# GPS_SATA.net
KiCad netlist of a schematic drawn in Altium Designer
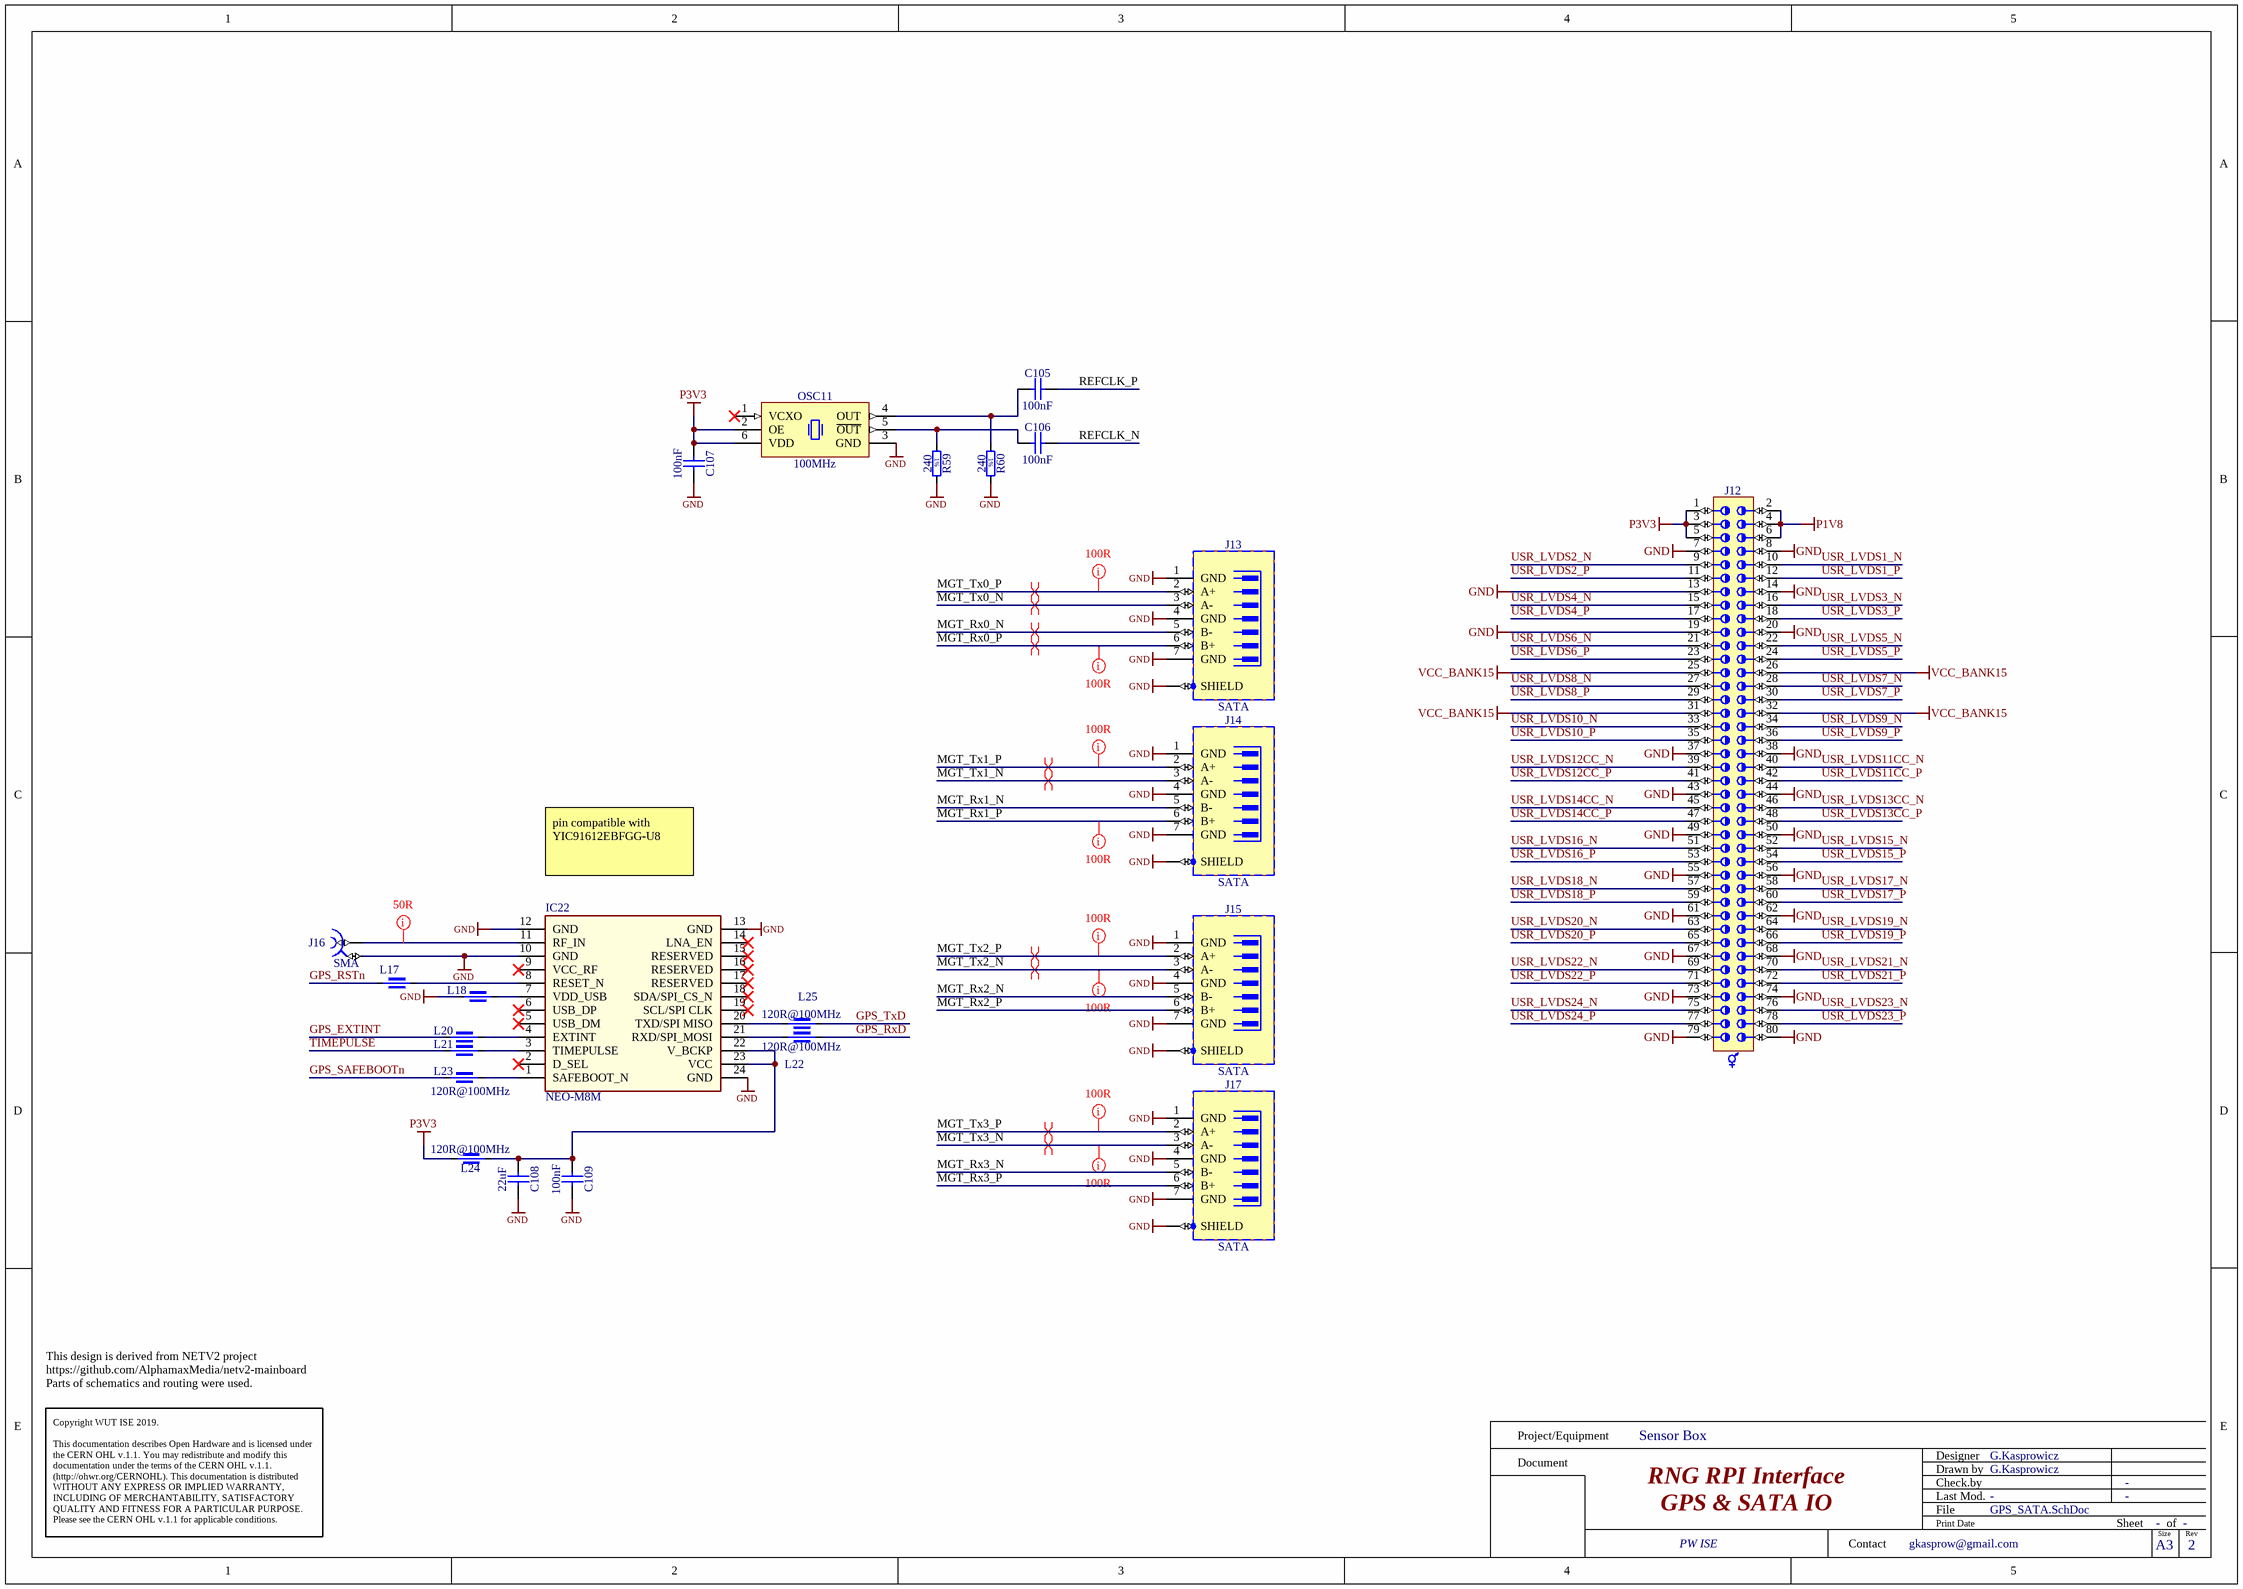
[diagram p0: GPS_SATA.SchDoc]

(export (version "E")
  (design (tool "Eeschema 10.0.6"))
  (components
    (comp (ref "C105")
      (value "100nF")
      (footprint "CAPC0603X33N")
      (description "Non-polarised capacitor")
      (fields
        (field (name "PART NUMBER") "CC0201_100NF_6.3V_10%_X5R")
        (field (name "VOLTAGE") "6.3V")
        (field (name "AUTHOR") "CERN DEM JLC")
      )
      (libsource (lib "Capacitors") (part "Capacitor - non polarized"))
    )
    (comp (ref "C106")
      (value "100nF")
      (footprint "CAPC0603X33N")
      (description "Non-polarised capacitor")
      (fields
        (field (name "PART NUMBER") "CC0201_100NF_6.3V_10%_X5R")
        (field (name "VOLTAGE") "6.3V")
        (field (name "AUTHOR") "CERN DEM JLC")
      )
      (libsource (lib "Capacitors") (part "Capacitor - non polarized"))
    )
    (comp (ref "C107")
      (value "100nF")
      (footprint "CAPC0603X33N")
      (description "Non-polarised capacitor")
      (fields
        (field (name "PART NUMBER") "CC0201_100NF_6.3V_10%_X5R")
        (field (name "VOLTAGE") "6.3V")
        (field (name "AUTHOR") "CERN DEM JLC")
      )
      (libsource (lib "Capacitors") (part "Capacitor - non polarized"))
    )
    (comp (ref "C108")
      (value "22uF")
      (footprint "CAPC2012X135N")
      (description "Non-polarised capacitor")
      (fields
        (field (name "PART NUMBER") "CC0805_22UF_16V_10%_X5R")
        (field (name "VOLTAGE") "16V")
        (field (name "AUTHOR") "CERN DEM JLC")
      )
      (libsource (lib "Capacitors") (part "Capacitor - non polarized"))
    )
    (comp (ref "C109")
      (value "100nF")
      (footprint "CAPC0603X33N")
      (description "Non-polarised capacitor")
      (fields
        (field (name "PART NUMBER") "CC0201_100NF_6.3V_10%_X5R")
        (field (name "VOLTAGE") "6.3V")
        (field (name "AUTHOR") "CERN DEM JLC")
      )
      (libsource (lib "Capacitors") (part "Capacitor - non polarized"))
    )
    (comp (ref "IC22")
      (value "NEO-M8M")
      (footprint "NEO")
      (description "u-blox NEO GNSS module")
      (fields (field (name "MANUFACTURER") "u-blox"))
      (libsource (lib "ubloxLib") (part "NEO"))
    )
    (comp (ref "J12")
      (value "~")
      (footprint "SAMTEC_LSS-140-01-L-DV-A")
      (description "Connector 80 Hermaphroditic")
      (fields
        (field (name "PART NUMBER") "SAMTEC_LSS-140-01-L-DV-A")
        (field (name "MANUFACTURER") "SAMTEC")
        (field (name "AUTHOR") "CERN DEM JMW")
      )
      (libsource (lib "Connectors") (part "Connector 80 Hermaphroditic"))
    )
    (comp (ref "J13")
      (value "SATA")
      (footprint "3M_5607-4200-SH")
      (description "7 Pin + 1 Shield SATA Receptacle")
      (fields
        (field (name "PART NUMBER") "3M_5607-4200-SH")
        (field (name "MANUFACTURER") "3M")
        (field (name "AUTHOR") "CERN DEM JLC")
      )
      (libsource (lib "Connectors") (part "Connector SATA 7 Male + 1 Shield"))
    )
    (comp (ref "J14")
      (value "SATA")
      (footprint "3M_5607-4200-SH")
      (description "7 Pin + 1 Shield SATA Receptacle")
      (fields
        (field (name "PART NUMBER") "3M_5607-4200-SH")
        (field (name "MANUFACTURER") "3M")
        (field (name "AUTHOR") "CERN DEM JLC")
      )
      (libsource (lib "Connectors") (part "Connector SATA 7 Male + 1 Shield"))
    )
    (comp (ref "J15")
      (value "SATA")
      (footprint "3M_5607-4200-SH")
      (description "7 Pin + 1 Shield SATA Receptacle")
      (fields
        (field (name "PART NUMBER") "3M_5607-4200-SH")
        (field (name "MANUFACTURER") "3M")
        (field (name "AUTHOR") "CERN DEM JLC")
      )
      (libsource (lib "Connectors") (part "Connector SATA 7 Male + 1 Shield"))
    )
    (comp (ref "J16")
      (value "SMA")
      (footprint "MOLEX_73251-2120")
      (description "50 Ohm, SMA Edge Mount PCB, With Jam Nut And Lock Washer")
      (fields
        (field (name "PART NUMBER") "MOLEX_73251-2120")
        (field (name "MANUFACTURER") "MOLEX")
        (field (name "AUTHOR") "CERN DEM JLC")
      )
      (libsource (lib "Connectors") (part "CON_SMA_RA_SMD_73251-2120"))
    )
    (comp (ref "J17")
      (value "SATA")
      (footprint "3M_5607-4200-SH")
      (description "7 Pin + 1 Shield SATA Receptacle")
      (fields
        (field (name "PART NUMBER") "3M_5607-4200-SH")
        (field (name "MANUFACTURER") "3M")
        (field (name "AUTHOR") "CERN DEM JLC")
      )
      (libsource (lib "Connectors") (part "Connector SATA 7 Male + 1 Shield"))
    )
    (comp (ref "L17")
      (value "120R@100MHz")
      (footprint "INDC1608X65N")
      (fields
        (field (name "PART NUMBER") "IND0603_MURATA_BLM18SG121TN1D")
        (field (name "POWER") "3A")
        (field (name "TOLERANCE") "±25%")
        (field (name "AUTHOR") "CERN DEM JLC")
      )
      (libsource (lib "") (part "Ferrite Bead_1"))
    )
    (comp (ref "L18")
      (value "120R@100MHz")
      (footprint "INDC1608X65N")
      (fields
        (field (name "PART NUMBER") "IND0603_MURATA_BLM18SG121TN1D")
        (field (name "POWER") "3A")
        (field (name "TOLERANCE") "±25%")
        (field (name "AUTHOR") "CERN DEM JLC")
      )
      (libsource (lib "Inductors & Transformers") (part "Ferrite Bead"))
    )
    (comp (ref "L20")
      (value "120R@100MHz")
      (footprint "INDC1608X65N")
      (fields
        (field (name "PART NUMBER") "IND0603_MURATA_BLM18SG121TN1D")
        (field (name "POWER") "3A")
        (field (name "TOLERANCE") "±25%")
        (field (name "AUTHOR") "CERN DEM JLC")
      )
      (libsource (lib "Inductors & Transformers") (part "Ferrite Bead"))
    )
    (comp (ref "L21")
      (value "120R@100MHz")
      (footprint "INDC1608X65N")
      (fields
        (field (name "PART NUMBER") "IND0603_MURATA_BLM18SG121TN1D")
        (field (name "POWER") "3A")
        (field (name "TOLERANCE") "±25%")
        (field (name "AUTHOR") "CERN DEM JLC")
      )
      (libsource (lib "Inductors & Transformers") (part "Ferrite Bead"))
    )
    (comp (ref "L22")
      (value "120R@100MHz")
      (footprint "INDC1608X65N")
      (fields
        (field (name "PART NUMBER") "IND0603_MURATA_BLM18SG121TN1D")
        (field (name "POWER") "3A")
        (field (name "TOLERANCE") "±25%")
        (field (name "AUTHOR") "CERN DEM JLC")
      )
      (libsource (lib "") (part "Ferrite Bead_1"))
    )
    (comp (ref "L23")
      (value "120R@100MHz")
      (footprint "INDC1608X65N")
      (fields
        (field (name "PART NUMBER") "IND0603_MURATA_BLM18SG121TN1D")
        (field (name "POWER") "3A")
        (field (name "TOLERANCE") "±25%")
        (field (name "AUTHOR") "CERN DEM JLC")
      )
      (libsource (lib "Inductors & Transformers") (part "Ferrite Bead"))
    )
    (comp (ref "L24")
      (value "120R@100MHz")
      (footprint "INDC1608X65N")
      (fields
        (field (name "PART NUMBER") "IND0603_MURATA_BLM18SG121TN1D")
        (field (name "POWER") "3A")
        (field (name "TOLERANCE") "±25%")
        (field (name "AUTHOR") "CERN DEM JLC")
      )
      (libsource (lib "Inductors & Transformers") (part "Ferrite Bead"))
    )
    (comp (ref "L25")
      (value "120R@100MHz")
      (footprint "INDC1608X65N")
      (fields
        (field (name "PART NUMBER") "IND0603_MURATA_BLM18SG121TN1D")
        (field (name "POWER") "3A")
        (field (name "TOLERANCE") "±25%")
        (field (name "AUTHOR") "CERN DEM JLC")
      )
      (libsource (lib "Inductors & Transformers") (part "Ferrite Bead"))
    )
    (comp (ref "OSC11")
      (value "100MHz")
      (footprint "OSCSC254P500X700X190-6N")
      (description "VCXO 100MHz Oscillator")
      (fields
        (field (name "PART NUMBER") "OSC_100MHZ_ABRACON_ASG-P-V-A-100.000MHZ")
        (field (name "MANUFACTURER") "ABRACON")
        (field (name "AUTHOR") "GK")
      )
      (libsource (lib "Crystals_Oscillators") (part "OSC_100MHz_LVPECL"))
    )
    (comp (ref "R59")
      (value "240")
      (footprint "RESC1005X40N")
      (description "Resistor - 1%")
      (fields
        (field (name "PART NUMBER") "R0402_240R_1%_0.0625W_100PPM")
        (field (name "POWER") "0.0625W")
        (field (name "AUTHOR") "CERN DEM JLC")
      )
      (libsource (lib "Resistors") (part "Resistor - 1%"))
    )
    (comp (ref "R60")
      (value "240")
      (footprint "RESC1005X40N")
      (description "Resistor - 1%")
      (fields
        (field (name "PART NUMBER") "R0402_240R_1%_0.0625W_100PPM")
        (field (name "POWER") "0.0625W")
        (field (name "AUTHOR") "CERN DEM JLC")
      )
      (libsource (lib "Resistors") (part "Resistor - 1%"))
    )
  )
  (nets
    (net (code "1") (name "/GPS_EXTINT") (class "Default")
      (node (ref "L20") (pin "2") (pinfunction "2_2") (pintype "passive"))
    )
    (net (code "2") (name "/GPS_RSTn") (class "Default")
      (node (ref "L17") (pin "1") (pinfunction "1_1") (pintype "passive"))
    )
    (net (code "3") (name "/GPS_RxD") (class "Default")
      (node (ref "L22") (pin "2") (pinfunction "2_2") (pintype "passive"))
    )
    (net (code "4") (name "/GPS_SAFEBOOTn") (class "Default")
      (node (ref "L23") (pin "2") (pinfunction "2_2") (pintype "passive"))
    )
    (net (code "5") (name "/GPS_TxD") (class "Default")
      (node (ref "L25") (pin "1") (pinfunction "1_1") (pintype "passive"))
    )
    (net (code "6") (name "/MGT_Rx0_N") (class "Default")
      (node (ref "J13") (pin "5") (pinfunction "B-_5") (pintype "bidirectional"))
    )
    (net (code "7") (name "/MGT_Rx0_P") (class "Default")
      (node (ref "J13") (pin "6") (pinfunction "B+_6") (pintype "bidirectional"))
    )
    (net (code "8") (name "/MGT_Rx1_N") (class "Default")
      (node (ref "J14") (pin "5") (pinfunction "B-_5") (pintype "bidirectional"))
    )
    (net (code "9") (name "/MGT_Rx1_P") (class "Default")
      (node (ref "J14") (pin "6") (pinfunction "B+_6") (pintype "bidirectional"))
    )
    (net (code "10") (name "/MGT_Rx2_N") (class "Default")
      (node (ref "J15") (pin "5") (pinfunction "B-_5") (pintype "bidirectional"))
    )
    (net (code "11") (name "/MGT_Rx2_P") (class "Default")
      (node (ref "J15") (pin "6") (pinfunction "B+_6") (pintype "bidirectional"))
    )
    (net (code "12") (name "/MGT_Rx3_N") (class "Default")
      (node (ref "J17") (pin "5") (pinfunction "B-_5") (pintype "bidirectional"))
    )
    (net (code "13") (name "/MGT_Rx3_P") (class "Default")
      (node (ref "J17") (pin "6") (pinfunction "B+_6") (pintype "bidirectional"))
    )
    (net (code "14") (name "/MGT_Tx0_N") (class "Default")
      (node (ref "J13") (pin "3") (pinfunction "A-_3") (pintype "bidirectional"))
    )
    (net (code "15") (name "/MGT_Tx0_P") (class "Default")
      (node (ref "J13") (pin "2") (pinfunction "A+_2") (pintype "bidirectional"))
    )
    (net (code "16") (name "/MGT_Tx1_N") (class "Default")
      (node (ref "J14") (pin "3") (pinfunction "A-_3") (pintype "bidirectional"))
    )
    (net (code "17") (name "/MGT_Tx1_P") (class "Default")
      (node (ref "J14") (pin "2") (pinfunction "A+_2") (pintype "bidirectional"))
    )
    (net (code "18") (name "/MGT_Tx2_N") (class "Default")
      (node (ref "J15") (pin "3") (pinfunction "A-_3") (pintype "bidirectional"))
    )
    (net (code "19") (name "/MGT_Tx2_P") (class "Default")
      (node (ref "J15") (pin "2") (pinfunction "A+_2") (pintype "bidirectional"))
    )
    (net (code "20") (name "/MGT_Tx3_N") (class "Default")
      (node (ref "J17") (pin "3") (pinfunction "A-_3") (pintype "bidirectional"))
    )
    (net (code "21") (name "/MGT_Tx3_P") (class "Default")
      (node (ref "J17") (pin "2") (pinfunction "A+_2") (pintype "bidirectional"))
    )
    (net (code "22") (name "/REFCLK_N") (class "Default")
      (node (ref "C106") (pin "2") (pinfunction "2_2") (pintype "passive"))
    )
    (net (code "23") (name "/REFCLK_P") (class "Default")
      (node (ref "C105") (pin "2") (pinfunction "2_2") (pintype "passive"))
    )
    (net (code "24") (name "/TIMEPULSE") (class "Default")
      (node (ref "L21") (pin "2") (pinfunction "2_2") (pintype "passive"))
    )
    (net (code "25") (name "/USR_LVDS1_N") (class "Default")
      (node (ref "J12") (pin "10") (pinfunction "10_10") (pintype "bidirectional"))
    )
    (net (code "26") (name "/USR_LVDS1_P") (class "Default")
      (node (ref "J12") (pin "12") (pinfunction "12_12") (pintype "bidirectional"))
    )
    (net (code "27") (name "/USR_LVDS2_N") (class "Default")
      (node (ref "J12") (pin "9") (pinfunction "9_9") (pintype "bidirectional"))
    )
    (net (code "28") (name "/USR_LVDS2_P") (class "Default")
      (node (ref "J12") (pin "11") (pinfunction "11_11") (pintype "bidirectional"))
    )
    (net (code "29") (name "/USR_LVDS3_N") (class "Default")
      (node (ref "J12") (pin "16") (pinfunction "16_16") (pintype "bidirectional"))
    )
    (net (code "30") (name "/USR_LVDS3_P") (class "Default")
      (node (ref "J12") (pin "18") (pinfunction "18_18") (pintype "bidirectional"))
    )
    (net (code "31") (name "/USR_LVDS4_N") (class "Default")
      (node (ref "J12") (pin "15") (pinfunction "15_15") (pintype "bidirectional"))
    )
    (net (code "32") (name "/USR_LVDS4_P") (class "Default")
      (node (ref "J12") (pin "17") (pinfunction "17_17") (pintype "bidirectional"))
    )
    (net (code "33") (name "/USR_LVDS5_N") (class "Default")
      (node (ref "J12") (pin "22") (pinfunction "22_22") (pintype "bidirectional"))
    )
    (net (code "34") (name "/USR_LVDS5_P") (class "Default")
      (node (ref "J12") (pin "24") (pinfunction "24_24") (pintype "bidirectional"))
    )
    (net (code "35") (name "/USR_LVDS6_N") (class "Default")
      (node (ref "J12") (pin "21") (pinfunction "21_21") (pintype "bidirectional"))
    )
    (net (code "36") (name "/USR_LVDS6_P") (class "Default")
      (node (ref "J12") (pin "23") (pinfunction "23_23") (pintype "bidirectional"))
    )
    (net (code "37") (name "/USR_LVDS7_N") (class "Default")
      (node (ref "J12") (pin "28") (pinfunction "28_28") (pintype "bidirectional"))
    )
    (net (code "38") (name "/USR_LVDS7_P") (class "Default")
      (node (ref "J12") (pin "30") (pinfunction "30_30") (pintype "bidirectional"))
    )
    (net (code "39") (name "/USR_LVDS8_N") (class "Default")
      (node (ref "J12") (pin "27") (pinfunction "27_27") (pintype "bidirectional"))
    )
    (net (code "40") (name "/USR_LVDS8_P") (class "Default")
      (node (ref "J12") (pin "29") (pinfunction "29_29") (pintype "bidirectional"))
    )
    (net (code "41") (name "/USR_LVDS9_N") (class "Default")
      (node (ref "J12") (pin "34") (pinfunction "34_34") (pintype "bidirectional"))
    )
    (net (code "42") (name "/USR_LVDS9_P") (class "Default")
      (node (ref "J12") (pin "36") (pinfunction "36_36") (pintype "bidirectional"))
    )
    (net (code "43") (name "/USR_LVDS10_N") (class "Default")
      (node (ref "J12") (pin "33") (pinfunction "33_33") (pintype "bidirectional"))
    )
    (net (code "44") (name "/USR_LVDS10_P") (class "Default")
      (node (ref "J12") (pin "35") (pinfunction "35_35") (pintype "bidirectional"))
    )
    (net (code "45") (name "/USR_LVDS11CC_N") (class "Default")
      (node (ref "J12") (pin "40") (pinfunction "40_40") (pintype "bidirectional"))
    )
    (net (code "46") (name "/USR_LVDS11CC_P") (class "Default")
      (node (ref "J12") (pin "42") (pinfunction "42_42") (pintype "bidirectional"))
    )
    (net (code "47") (name "/USR_LVDS12CC_N") (class "Default")
      (node (ref "J12") (pin "39") (pinfunction "39_39") (pintype "bidirectional"))
    )
    (net (code "48") (name "/USR_LVDS12CC_P") (class "Default")
      (node (ref "J12") (pin "41") (pinfunction "41_41") (pintype "bidirectional"))
    )
    (net (code "49") (name "/USR_LVDS13CC_N") (class "Default")
      (node (ref "J12") (pin "46") (pinfunction "46_46") (pintype "bidirectional"))
    )
    (net (code "50") (name "/USR_LVDS13CC_P") (class "Default")
      (node (ref "J12") (pin "48") (pinfunction "48_48") (pintype "bidirectional"))
    )
    (net (code "51") (name "/USR_LVDS14CC_N") (class "Default")
      (node (ref "J12") (pin "45") (pinfunction "45_45") (pintype "bidirectional"))
    )
    (net (code "52") (name "/USR_LVDS14CC_P") (class "Default")
      (node (ref "J12") (pin "47") (pinfunction "47_47") (pintype "bidirectional"))
    )
    (net (code "53") (name "/USR_LVDS15_N") (class "Default")
      (node (ref "J12") (pin "52") (pinfunction "52_52") (pintype "bidirectional"))
    )
    (net (code "54") (name "/USR_LVDS15_P") (class "Default")
      (node (ref "J12") (pin "54") (pinfunction "54_54") (pintype "bidirectional"))
    )
    (net (code "55") (name "/USR_LVDS16_N") (class "Default")
      (node (ref "J12") (pin "51") (pinfunction "51_51") (pintype "bidirectional"))
    )
    (net (code "56") (name "/USR_LVDS16_P") (class "Default")
      (node (ref "J12") (pin "53") (pinfunction "53_53") (pintype "bidirectional"))
    )
    (net (code "57") (name "/USR_LVDS17_N") (class "Default")
      (node (ref "J12") (pin "58") (pinfunction "58_58") (pintype "bidirectional"))
    )
    (net (code "58") (name "/USR_LVDS17_P") (class "Default")
      (node (ref "J12") (pin "60") (pinfunction "60_60") (pintype "bidirectional"))
    )
    (net (code "59") (name "/USR_LVDS18_N") (class "Default")
      (node (ref "J12") (pin "57") (pinfunction "57_57") (pintype "bidirectional"))
    )
    (net (code "60") (name "/USR_LVDS18_P") (class "Default")
      (node (ref "J12") (pin "59") (pinfunction "59_59") (pintype "bidirectional"))
    )
    (net (code "61") (name "/USR_LVDS19_N") (class "Default")
      (node (ref "J12") (pin "64") (pinfunction "64_64") (pintype "bidirectional"))
    )
    (net (code "62") (name "/USR_LVDS19_P") (class "Default")
      (node (ref "J12") (pin "66") (pinfunction "66_66") (pintype "bidirectional"))
    )
    (net (code "63") (name "/USR_LVDS20_N") (class "Default")
      (node (ref "J12") (pin "63") (pinfunction "63_63") (pintype "bidirectional"))
    )
    (net (code "64") (name "/USR_LVDS20_P") (class "Default")
      (node (ref "J12") (pin "65") (pinfunction "65_65") (pintype "bidirectional"))
    )
    (net (code "65") (name "/USR_LVDS21_N") (class "Default")
      (node (ref "J12") (pin "70") (pinfunction "70_70") (pintype "bidirectional"))
    )
    (net (code "66") (name "/USR_LVDS21_P") (class "Default")
      (node (ref "J12") (pin "72") (pinfunction "72_72") (pintype "bidirectional"))
    )
    (net (code "67") (name "/USR_LVDS22_N") (class "Default")
      (node (ref "J12") (pin "69") (pinfunction "69_69") (pintype "bidirectional"))
    )
    (net (code "68") (name "/USR_LVDS22_P") (class "Default")
      (node (ref "J12") (pin "71") (pinfunction "71_71") (pintype "bidirectional"))
    )
    (net (code "69") (name "/USR_LVDS23_N") (class "Default")
      (node (ref "J12") (pin "76") (pinfunction "76_76") (pintype "bidirectional"))
    )
    (net (code "70") (name "/USR_LVDS23_P") (class "Default")
      (node (ref "J12") (pin "78") (pinfunction "78_78") (pintype "bidirectional"))
    )
    (net (code "71") (name "/USR_LVDS24_N") (class "Default")
      (node (ref "J12") (pin "75") (pinfunction "75_75") (pintype "bidirectional"))
    )
    (net (code "72") (name "/USR_LVDS24_P") (class "Default")
      (node (ref "J12") (pin "77") (pinfunction "77_77") (pintype "bidirectional"))
    )
    (net (code "73") (name "GND") (class "Default")
      (node (ref "C107") (pin "2") (pinfunction "2_2") (pintype "passive"))
      (node (ref "C108") (pin "2") (pinfunction "2_2") (pintype "passive"))
      (node (ref "C109") (pin "2") (pinfunction "2_2") (pintype "passive"))
      (node (ref "IC22") (pin "10") (pinfunction "GND_10") (pintype "passive"))
      (node (ref "IC22") (pin "12") (pinfunction "GND_12") (pintype "passive"))
      (node (ref "IC22") (pin "13") (pinfunction "GND_13") (pintype "passive"))
      (node (ref "IC22") (pin "24") (pinfunction "GND_24") (pintype "passive"))
      (node (ref "J12") (pin "13") (pinfunction "13_13") (pintype "bidirectional"))
      (node (ref "J12") (pin "14") (pinfunction "14_14") (pintype "bidirectional"))
      (node (ref "J12") (pin "19") (pinfunction "19_19") (pintype "bidirectional"))
      (node (ref "J12") (pin "20") (pinfunction "20_20") (pintype "bidirectional"))
      (node (ref "J12") (pin "37") (pinfunction "37_37") (pintype "bidirectional"))
      (node (ref "J12") (pin "38") (pinfunction "38_38") (pintype "bidirectional"))
      (node (ref "J12") (pin "43") (pinfunction "43_43") (pintype "bidirectional"))
      (node (ref "J12") (pin "44") (pinfunction "44_44") (pintype "bidirectional"))
      (node (ref "J12") (pin "49") (pinfunction "49_49") (pintype "bidirectional"))
      (node (ref "J12") (pin "50") (pinfunction "50_50") (pintype "bidirectional"))
      (node (ref "J12") (pin "55") (pinfunction "55_55") (pintype "bidirectional"))
      (node (ref "J12") (pin "56") (pinfunction "56_56") (pintype "bidirectional"))
      (node (ref "J12") (pin "61") (pinfunction "61_61") (pintype "bidirectional"))
      (node (ref "J12") (pin "62") (pinfunction "62_62") (pintype "bidirectional"))
      (node (ref "J12") (pin "67") (pinfunction "67_67") (pintype "bidirectional"))
      (node (ref "J12") (pin "68") (pinfunction "68_68") (pintype "bidirectional"))
      (node (ref "J12") (pin "7") (pinfunction "7_7") (pintype "bidirectional"))
      (node (ref "J12") (pin "73") (pinfunction "73_73") (pintype "bidirectional"))
      (node (ref "J12") (pin "74") (pinfunction "74_74") (pintype "bidirectional"))
      (node (ref "J12") (pin "79") (pinfunction "79_79") (pintype "bidirectional"))
      (node (ref "J12") (pin "8") (pinfunction "8_8") (pintype "bidirectional"))
      (node (ref "J12") (pin "80") (pinfunction "80_80") (pintype "bidirectional"))
      (node (ref "J13") (pin "1") (pinfunction "GND_1") (pintype "power_in"))
      (node (ref "J13") (pin "4") (pinfunction "GND_4") (pintype "power_in"))
      (node (ref "J13") (pin "7") (pinfunction "GND_7") (pintype "power_in"))
      (node (ref "J13") (pin "8") (pinfunction "SHIELD_8") (pintype "bidirectional"))
      (node (ref "J14") (pin "1") (pinfunction "GND_1") (pintype "power_in"))
      (node (ref "J14") (pin "4") (pinfunction "GND_4") (pintype "power_in"))
      (node (ref "J14") (pin "7") (pinfunction "GND_7") (pintype "power_in"))
      (node (ref "J14") (pin "8") (pinfunction "SHIELD_8") (pintype "bidirectional"))
      (node (ref "J15") (pin "1") (pinfunction "GND_1") (pintype "power_in"))
      (node (ref "J15") (pin "4") (pinfunction "GND_4") (pintype "power_in"))
      (node (ref "J15") (pin "7") (pinfunction "GND_7") (pintype "power_in"))
      (node (ref "J15") (pin "8") (pinfunction "SHIELD_8") (pintype "bidirectional"))
      (node (ref "J16") (pin "2") (pinfunction "2_2") (pintype "bidirectional"))
      (node (ref "J17") (pin "1") (pinfunction "GND_1") (pintype "power_in"))
      (node (ref "J17") (pin "4") (pinfunction "GND_4") (pintype "power_in"))
      (node (ref "J17") (pin "7") (pinfunction "GND_7") (pintype "power_in"))
      (node (ref "J17") (pin "8") (pinfunction "SHIELD_8") (pintype "bidirectional"))
      (node (ref "L18") (pin "2") (pinfunction "2_2") (pintype "passive"))
      (node (ref "OSC11") (pin "3") (pinfunction "GND_3") (pintype "power_in"))
      (node (ref "R59") (pin "2") (pinfunction "2_2") (pintype "passive"))
      (node (ref "R60") (pin "2") (pinfunction "2_2") (pintype "passive"))
    )
    (net (code "74") (name "Net-(IC22-EXTINT)") (class "Default")
      (node (ref "IC22") (pin "4") (pinfunction "EXTINT_4") (pintype "passive"))
      (node (ref "L20") (pin "1") (pinfunction "1_1") (pintype "passive"))
    )
    (net (code "75") (name "Net-(IC22-RESET_N)") (class "Default")
      (node (ref "IC22") (pin "8") (pinfunction "RESET_N_8") (pintype "passive"))
      (node (ref "L17") (pin "2") (pinfunction "2_2") (pintype "passive"))
    )
    (net (code "76") (name "Net-(IC22-RF_IN)") (class "Default")
      (node (ref "IC22") (pin "11") (pinfunction "RF_IN_11") (pintype "passive"))
      (node (ref "J16") (pin "1") (pinfunction "1_1") (pintype "bidirectional"))
    )
    (net (code "77") (name "Net-(IC22-RXD{slash}SPI_MOSI)") (class "Default")
      (node (ref "IC22") (pin "21") (pinfunction "RXD/SPI_MOSI_21") (pintype "passive"))
      (node (ref "L22") (pin "1") (pinfunction "1_1") (pintype "passive"))
    )
    (net (code "78") (name "Net-(IC22-SAFEBOOT_N)") (class "Default")
      (node (ref "IC22") (pin "1") (pinfunction "SAFEBOOT_N_1") (pintype "passive"))
      (node (ref "L23") (pin "1") (pinfunction "1_1") (pintype "passive"))
    )
    (net (code "79") (name "Net-(IC22-TIMEPULSE)") (class "Default")
      (node (ref "IC22") (pin "3") (pinfunction "TIMEPULSE_3") (pintype "passive"))
      (node (ref "L21") (pin "1") (pinfunction "1_1") (pintype "passive"))
    )
    (net (code "80") (name "Net-(IC22-TXD{slash}SPI_MISO)") (class "Default")
      (node (ref "IC22") (pin "20") (pinfunction "TXD/SPI_MISO_20") (pintype "passive"))
      (node (ref "L25") (pin "2") (pinfunction "2_2") (pintype "passive"))
    )
    (net (code "81") (name "Net-(IC22-VCC)") (class "Default")
      (node (ref "C108") (pin "1") (pinfunction "1_1") (pintype "passive"))
      (node (ref "C109") (pin "1") (pinfunction "1_1") (pintype "passive"))
      (node (ref "IC22") (pin "22") (pinfunction "V_BCKP_22") (pintype "passive"))
      (node (ref "IC22") (pin "23") (pinfunction "VCC_23") (pintype "passive"))
      (node (ref "L24") (pin "1") (pinfunction "1_1") (pintype "passive"))
    )
    (net (code "82") (name "Net-(IC22-VDD_USB)") (class "Default")
      (node (ref "IC22") (pin "7") (pinfunction "VDD_USB_7") (pintype "passive"))
      (node (ref "L18") (pin "1") (pinfunction "1_1") (pintype "passive"))
    )
    (net (code "83") (name "Net-(OSC11-OUT)") (class "Default")
      (node (ref "C105") (pin "1") (pinfunction "1_1") (pintype "passive"))
      (node (ref "OSC11") (pin "4") (pinfunction "OUT_4") (pintype "output"))
      (node (ref "R60") (pin "1") (pinfunction "1_1") (pintype "passive"))
    )
    (net (code "84") (name "Net-(OSC11-~{OUT})") (class "Default")
      (node (ref "C106") (pin "1") (pinfunction "1_1") (pintype "passive"))
      (node (ref "OSC11") (pin "5") (pinfunction "~{OUT}_5") (pintype "output"))
      (node (ref "R59") (pin "1") (pinfunction "1_1") (pintype "passive"))
    )
    (net (code "85") (name "P1V8") (class "Default")
      (node (ref "J12") (pin "2") (pinfunction "2_2") (pintype "bidirectional"))
      (node (ref "J12") (pin "4") (pinfunction "4_4") (pintype "bidirectional"))
      (node (ref "J12") (pin "6") (pinfunction "6_6") (pintype "bidirectional"))
    )
    (net (code "86") (name "P3V3") (class "Default")
      (node (ref "C107") (pin "1") (pinfunction "1_1") (pintype "passive"))
      (node (ref "J12") (pin "1") (pinfunction "1_1") (pintype "bidirectional"))
      (node (ref "J12") (pin "3") (pinfunction "3_3") (pintype "bidirectional"))
      (node (ref "J12") (pin "5") (pinfunction "5_5") (pintype "bidirectional"))
      (node (ref "L24") (pin "2") (pinfunction "2_2") (pintype "passive"))
      (node (ref "OSC11") (pin "2") (pinfunction "OE_2") (pintype "passive"))
      (node (ref "OSC11") (pin "6") (pinfunction "VDD_6") (pintype "power_in"))
    )
    (net (code "87") (name "VCC_BANK15") (class "Default")
      (node (ref "J12") (pin "25") (pinfunction "25_25") (pintype "bidirectional"))
      (node (ref "J12") (pin "26") (pinfunction "26_26") (pintype "bidirectional"))
      (node (ref "J12") (pin "31") (pinfunction "31_31") (pintype "bidirectional"))
      (node (ref "J12") (pin "32") (pinfunction "32_32") (pintype "bidirectional"))
    )
    (net (code "88") (name "unconnected-(IC22-D_SEL-Pad2)") (class "Default")
      (node (ref "IC22") (pin "2") (pinfunction "D_SEL_2") (pintype "passive+no_connect"))
    )
    (net (code "89") (name "unconnected-(IC22-LNA_EN-Pad14)") (class "Default")
      (node (ref "IC22") (pin "14") (pinfunction "LNA_EN_14") (pintype "passive+no_connect"))
    )
    (net (code "90") (name "unconnected-(IC22-RESERVED-Pad15)") (class "Default")
      (node (ref "IC22") (pin "15") (pinfunction "RESERVED_15") (pintype "passive+no_connect"))
    )
    (net (code "91") (name "unconnected-(IC22-RESERVED-Pad16)") (class "Default")
      (node (ref "IC22") (pin "16") (pinfunction "RESERVED_16") (pintype "passive+no_connect"))
    )
    (net (code "92") (name "unconnected-(IC22-RESERVED-Pad17)") (class "Default")
      (node (ref "IC22") (pin "17") (pinfunction "RESERVED_17") (pintype "passive+no_connect"))
    )
    (net (code "93") (name "unconnected-(IC22-SCL{slash}SPI_CLK-Pad19)") (class "Default")
      (node (ref "IC22") (pin "19") (pinfunction "SCL/SPI_CLK_19") (pintype "passive+no_connect"))
    )
    (net (code "94") (name "unconnected-(IC22-SDA{slash}SPI_CS_N-Pad18)") (class "Default")
      (node (ref "IC22") (pin "18") (pinfunction "SDA/SPI_CS_N_18") (pintype "passive+no_connect"))
    )
    (net (code "95") (name "unconnected-(IC22-USB_DM-Pad5)") (class "Default")
      (node (ref "IC22") (pin "5") (pinfunction "USB_DM_5") (pintype "passive+no_connect"))
    )
    (net (code "96") (name "unconnected-(IC22-USB_DP-Pad6)") (class "Default")
      (node (ref "IC22") (pin "6") (pinfunction "USB_DP_6") (pintype "passive+no_connect"))
    )
    (net (code "97") (name "unconnected-(IC22-VCC_RF-Pad9)") (class "Default")
      (node (ref "IC22") (pin "9") (pinfunction "VCC_RF_9") (pintype "passive+no_connect"))
    )
    (net (code "98") (name "unconnected-(OSC11-VCXO-Pad1)") (class "Default")
      (node (ref "OSC11") (pin "1") (pinfunction "VCXO_1") (pintype "input+no_connect"))
    )
  )
)
